# MCU.net
KiCad netlist of a schematic drawn in Altium Designer
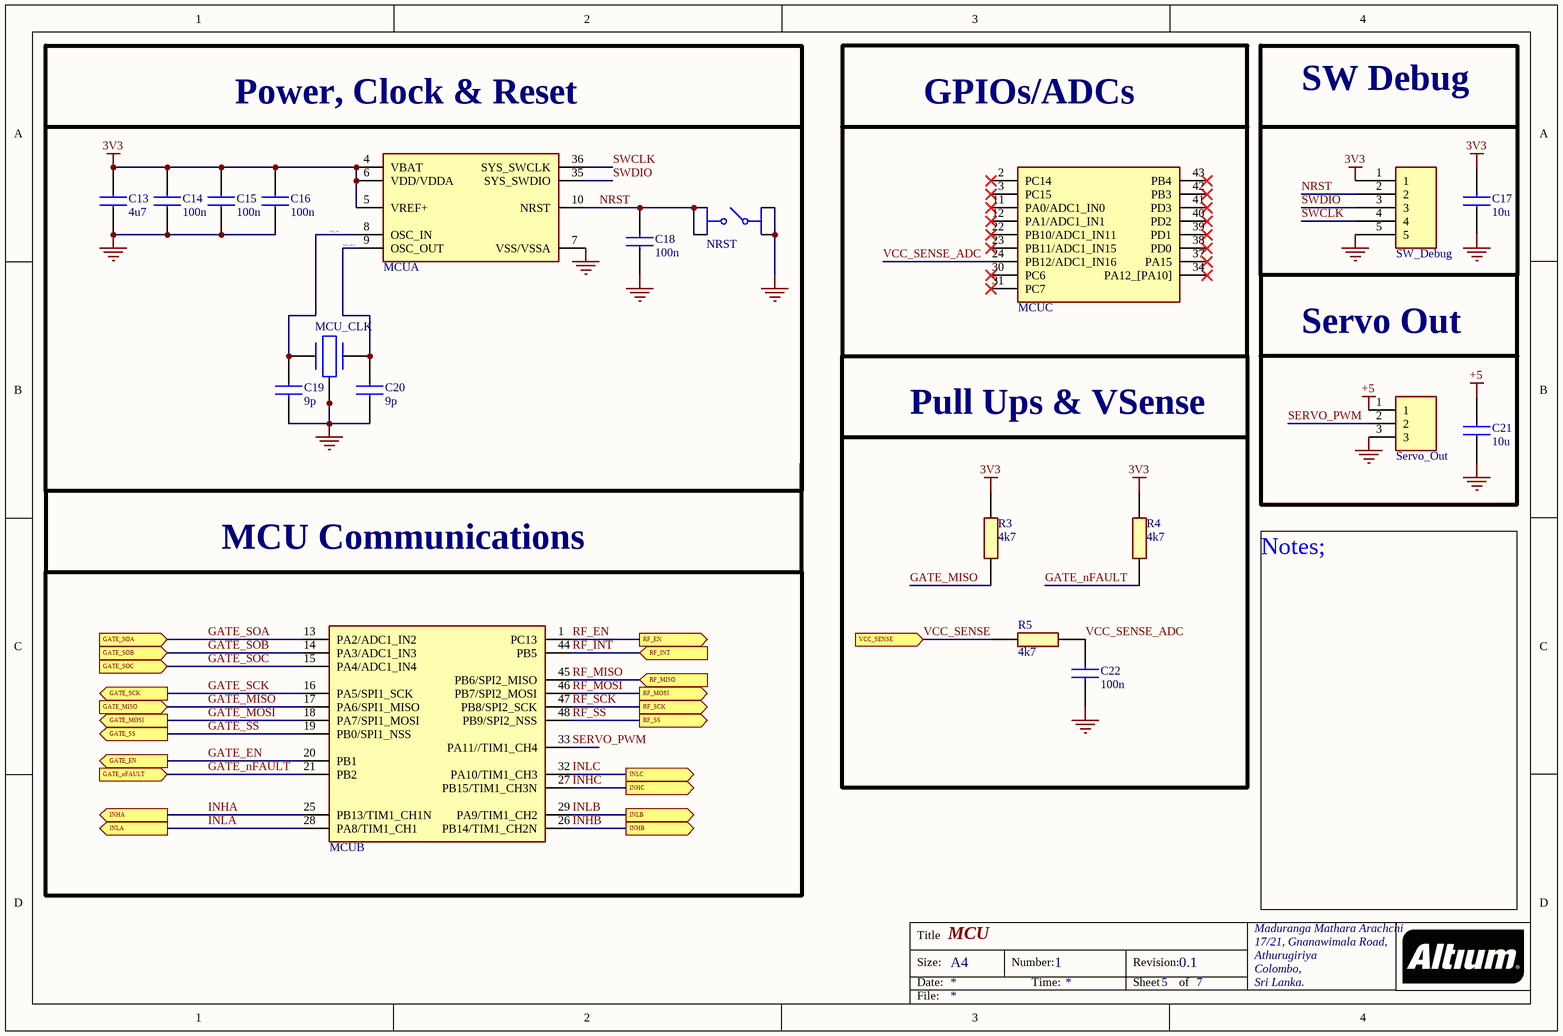
[diagram p0: MCU.SchDoc]

(export (version "E")
  (design (tool "Eeschema 10.0.6"))
  (components
    (comp (ref "C13")
      (value "4u7")
      (footprint "RC_Car:CAPC1608X90N")
      (description "Capacitor")
      (fields
        (field (name "MANUFACTURER_PART_NUMBER") "GRM188R61E475ME11J")
        (field (name "MOUSER PART NUMBER") "81-GRM188R61E475ME1J")
      )
      (libsource (lib "RC_Car") (part "GRM188R61E475ME11J"))
    )
    (comp (ref "C14")
      (value "100n")
      (footprint "RC_Car:GRM18x")
      (description "Capacitor")
      (fields
        (field (name "MANUFACTURER_PART_NUMBER") "GRM188R72A104KA35D")
        (field (name "MOUSER PART NUMBER") "81-GRM188R72A104KA35")
      )
      (libsource (lib "RC_Car") (part "GRM188R72A104KA35D"))
    )
    (comp (ref "C15")
      (value "100n")
      (footprint "RC_Car:GRM18x")
      (description "Capacitor")
      (fields
        (field (name "MANUFACTURER_PART_NUMBER") "GRM188R72A104KA35D")
        (field (name "MOUSER PART NUMBER") "81-GRM188R72A104KA35")
      )
      (libsource (lib "RC_Car") (part "GRM188R72A104KA35D"))
    )
    (comp (ref "C16")
      (value "100n")
      (footprint "RC_Car:GRM18x")
      (description "Capacitor")
      (fields
        (field (name "MANUFACTURER_PART_NUMBER") "GRM188R72A104KA35D")
        (field (name "MOUSER PART NUMBER") "81-GRM188R72A104KA35")
      )
      (libsource (lib "RC_Car") (part "GRM188R72A104KA35D"))
    )
    (comp (ref "C17")
      (value "10u")
      (footprint "RC_Car:CAPC1608X90N")
      (description "Capacitor")
      (fields (field (name "MANUFACTURER_PART_NUMBER") "C0603C106M9PAC-TU"))
      (libsource (lib "RC_Car") (part "C0603C106M9PAC-TU"))
    )
    (comp (ref "C18")
      (value "100n")
      (footprint "RC_Car:GRM18x")
      (description "Capacitor")
      (fields
        (field (name "MANUFACTURER_PART_NUMBER") "GRM188R72A104KA35D")
        (field (name "MOUSER PART NUMBER") "81-GRM188R72A104KA35")
      )
      (libsource (lib "RC_Car") (part "GRM188R72A104KA35D"))
    )
    (comp (ref "C19")
      (value "9p")
      (footprint "RC_Car:CAPC1005X70N")
      (description "Capacitor")
      (fields (field (name "MANUFACTURER_PART_NUMBER") "GRM1555C1E9R0WA01J"))
      (libsource (lib "RC_Car") (part "GRM1555C1E9R0WA01J"))
    )
    (comp (ref "C20")
      (value "9p")
      (footprint "RC_Car:CAPC1005X70N")
      (description "Capacitor")
      (fields (field (name "MANUFACTURER_PART_NUMBER") "GRM1555C1E9R0WA01J"))
      (libsource (lib "RC_Car") (part "GRM1555C1E9R0WA01J"))
    )
    (comp (ref "C21")
      (value "10u")
      (footprint "RC_Car:CAPC1608X90N")
      (description "Capacitor")
      (fields (field (name "MANUFACTURER_PART_NUMBER") "C0603C106M9PAC-TU"))
      (libsource (lib "RC_Car") (part "C0603C106M9PAC-TU"))
    )
    (comp (ref "C22")
      (value "100n")
      (footprint "RC_Car:GRM18x")
      (description "Capacitor")
      (fields
        (field (name "MANUFACTURER_PART_NUMBER") "GRM188R72A104KA35D")
        (field (name "MOUSER PART NUMBER") "81-GRM188R72A104KA35")
      )
      (libsource (lib "RC_Car") (part "GRM188R72A104KA35D"))
    )
    (comp (ref "MCU")
      (value "STM32G070CBT6TR")
      (footprint "RC_Car:QFP50P900X900X160-48N")
      (description "Integrated Circuit")
      (fields (field (name "MOUSER PART NUMBER") "511-STM32G070CBT6TR"))
      (libsource (lib "RC_Car") (part "STM32G070CBT6TR"))
    )
    (comp (ref "MCU_CLK")
      (value "TSX-3225_16.0000MF18X-AC0")
      (footprint "RC_Car:TSX3225160000MF18XAC0")
      (description "16MHz Crystal")
      (fields
        (field (name "MANUFACTURER_PART_NUMBER") "TSX-3225 16.0000MF18X-AC0")
        (field (name "MOUSER PART NUMBER") "732-322516F18XAC0")
      )
      (libsource (lib "RC_Car") (part "TSX-3225_16.0000MF18X-AC0"))
    )
    (comp (ref "NRST")
      (value "PTS647SM50SMTR2N_LFS")
      (footprint "RC_Car:PTS647SK50SMTR2LFS")
      (description "Switch (4-Pin Push)")
      (fields (field (name "MANUFACTURER_PART_NUMBER") "PTS647SM50SMTR2N LFS"))
      (libsource (lib "RC_Car") (part "PTS647SM50SMTR2N_LFS"))
    )
    (comp (ref "R3")
      (value "4k7")
      (footprint "RC_Car:RESC1608X50N")
      (description "Resistor")
      (fields
        (field (name "MANUFACTURER_PART_NUMBER") "CRCW06034K70FKEC")
        (field (name "MOUSER PART NUMBER") "71-CRCW06034K70FKEC")
      )
      (libsource (lib "RC_Car") (part "CRCW06034K70FKEC"))
    )
    (comp (ref "R4")
      (value "4k7")
      (footprint "RC_Car:RESC1608X50N")
      (description "Resistor")
      (fields
        (field (name "MANUFACTURER_PART_NUMBER") "CRCW06034K70FKEC")
        (field (name "MOUSER PART NUMBER") "71-CRCW06034K70FKEC")
      )
      (libsource (lib "RC_Car") (part "CRCW06034K70FKEC"))
    )
    (comp (ref "R5")
      (value "4k7")
      (footprint "RC_Car:RESC1608X50N")
      (description "Resistor")
      (fields
        (field (name "MANUFACTURER_PART_NUMBER") "CRCW06034K70FKEC")
        (field (name "MOUSER PART NUMBER") "71-CRCW06034K70FKEC")
      )
      (libsource (lib "") (part "CRCW06034K70FKEC_1"))
    )
    (comp (ref "Servo_Out")
      (value "929850-01-03-RA")
      (footprint "RC_Car:RHDR3W76P0X254_1X3_762X254X826P")
      (description "Header")
      (fields (field (name "MOUSER PART NUMBER") "517-929850-01-03-RA"))
      (libsource (lib "RC_Car") (part "929850-01-03-RA"))
    )
    (comp (ref "SW_Debug")
      (value "SW Debug")
      (footprint "SW_Debug")
      (libsource (lib "RC_Car") (part "Debug Pads"))
    )
  )
  (nets
    (net (code "1") (name "+5") (class "Default")
      (node (ref "C21") (pin "2") (pinfunction "2_2") (pintype "passive"))
      (node (ref "Servo_Out") (pin "1") (pinfunction "1_1") (pintype "passive"))
    )
    (net (code "2") (name "/GATE_EN") (class "Default")
      (node (ref "MCU") (pin "20") (pinfunction "PB1_20") (pintype "passive"))
    )
    (net (code "3") (name "/GATE_MISO") (class "Default")
      (node (ref "MCU") (pin "17") (pinfunction "PA6/SPI1_MISO_17") (pintype "passive"))
      (node (ref "R3") (pin "1") (pinfunction "1_1") (pintype "passive"))
    )
    (net (code "4") (name "/GATE_MOSI") (class "Default")
      (node (ref "MCU") (pin "18") (pinfunction "PA7/SPI1_MOSI_18") (pintype "passive"))
    )
    (net (code "5") (name "/GATE_SCK") (class "Default")
      (node (ref "MCU") (pin "16") (pinfunction "PA5/SPI1_SCK_16") (pintype "passive"))
    )
    (net (code "6") (name "/GATE_SOA") (class "Default")
      (node (ref "MCU") (pin "13") (pinfunction "PA2/ADC1_IN2_13") (pintype "passive"))
    )
    (net (code "7") (name "/GATE_SOB") (class "Default")
      (node (ref "MCU") (pin "14") (pinfunction "PA3/ADC1_IN3_14") (pintype "passive"))
    )
    (net (code "8") (name "/GATE_SOC") (class "Default")
      (node (ref "MCU") (pin "15") (pinfunction "PA4/ADC1_IN4_15") (pintype "passive"))
    )
    (net (code "9") (name "/GATE_SS") (class "Default")
      (node (ref "MCU") (pin "19") (pinfunction "PB0/SPI1_NSS_19") (pintype "passive"))
    )
    (net (code "10") (name "/GATE_nFAULT") (class "Default")
      (node (ref "MCU") (pin "21") (pinfunction "PB2_21") (pintype "passive"))
      (node (ref "R4") (pin "1") (pinfunction "1_1") (pintype "passive"))
    )
    (net (code "11") (name "/INHA") (class "Default")
      (node (ref "MCU") (pin "25") (pinfunction "PB13/TIM1_CH1N_25") (pintype "passive"))
    )
    (net (code "12") (name "/INHB") (class "Default")
      (node (ref "MCU") (pin "26") (pinfunction "PB14/TIM1_CH2N_26") (pintype "passive"))
    )
    (net (code "13") (name "/INHC") (class "Default")
      (node (ref "MCU") (pin "27") (pinfunction "PB15/TIM1_CH3N_27") (pintype "passive"))
    )
    (net (code "14") (name "/INLA") (class "Default")
      (node (ref "MCU") (pin "28") (pinfunction "PA8/TIM1_CH1_28") (pintype "passive"))
    )
    (net (code "15") (name "/INLB") (class "Default")
      (node (ref "MCU") (pin "29") (pinfunction "PA9/TIM1_CH2_29") (pintype "passive"))
    )
    (net (code "16") (name "/INLC") (class "Default")
      (node (ref "MCU") (pin "32") (pinfunction "PA10/TIM1_CH3_32") (pintype "passive"))
    )
    (net (code "17") (name "/NRST") (class "Default")
      (node (ref "C18") (pin "2") (pinfunction "2_2") (pintype "passive"))
      (node (ref "MCU") (pin "10") (pinfunction "NRST_10") (pintype "passive"))
      (node (ref "NRST") (pin "1") (pinfunction "NO_1_1") (pintype "passive"))
      (node (ref "NRST") (pin "2") (pinfunction "NO_2_2") (pintype "passive"))
      (node (ref "SW_Debug") (pin "2") (pinfunction "2_2") (pintype "passive"))
    )
    (net (code "18") (name "/OSC_IN") (class "Default")
      (node (ref "C19") (pin "2") (pinfunction "2_2") (pintype "passive"))
      (node (ref "MCU") (pin "8") (pinfunction "OSC_IN_8") (pintype "passive"))
      (node (ref "MCU_CLK") (pin "1") (pinfunction "CRYSTAL_1_1") (pintype "passive"))
    )
    (net (code "19") (name "/OSC_OUT") (class "Default")
      (node (ref "C20") (pin "2") (pinfunction "2_2") (pintype "passive"))
      (node (ref "MCU") (pin "9") (pinfunction "OSC_OUT_9") (pintype "passive"))
      (node (ref "MCU_CLK") (pin "3") (pinfunction "CRYSTAL_2_3") (pintype "passive"))
    )
    (net (code "20") (name "/RF_EN") (class "Default")
      (node (ref "MCU") (pin "1") (pinfunction "PC13_1") (pintype "passive"))
    )
    (net (code "21") (name "/RF_INT") (class "Default")
      (node (ref "MCU") (pin "44") (pinfunction "PB5_44") (pintype "passive"))
    )
    (net (code "22") (name "/RF_MISO") (class "Default")
      (node (ref "MCU") (pin "45") (pinfunction "PB6/SPI2_MISO_45") (pintype "passive"))
    )
    (net (code "23") (name "/RF_MOSI") (class "Default")
      (node (ref "MCU") (pin "46") (pinfunction "PB7/SPI2_MOSI_46") (pintype "passive"))
    )
    (net (code "24") (name "/RF_SCK") (class "Default")
      (node (ref "MCU") (pin "47") (pinfunction "PB8/SPI2_SCK_47") (pintype "passive"))
    )
    (net (code "25") (name "/RF_SS") (class "Default")
      (node (ref "MCU") (pin "48") (pinfunction "PB9/SPI2_NSS_48") (pintype "passive"))
    )
    (net (code "26") (name "/SERVO_PWM") (class "Default")
      (node (ref "MCU") (pin "33") (pinfunction "PA11//TIM1_CH4_33") (pintype "passive"))
      (node (ref "Servo_Out") (pin "2") (pinfunction "2_2") (pintype "passive"))
    )
    (net (code "27") (name "/SWCLK") (class "Default")
      (node (ref "MCU") (pin "36") (pinfunction "SYS_SWCLK_36") (pintype "passive"))
      (node (ref "SW_Debug") (pin "4") (pinfunction "4_4") (pintype "passive"))
    )
    (net (code "28") (name "/SWDIO") (class "Default")
      (node (ref "MCU") (pin "35") (pinfunction "SYS_SWDIO_35") (pintype "passive"))
      (node (ref "SW_Debug") (pin "3") (pinfunction "3_3") (pintype "passive"))
    )
    (net (code "29") (name "/VCC_SENSE") (class "Default")
      (node (ref "R5") (pin "2") (pinfunction "2_2") (pintype "passive"))
    )
    (net (code "30") (name "/VCC_SENSE_ADC") (class "Default")
      (node (ref "C22") (pin "2") (pinfunction "2_2") (pintype "passive"))
      (node (ref "MCU") (pin "24") (pinfunction "PB12/ADC1_IN16_24") (pintype "passive"))
      (node (ref "R5") (pin "1") (pinfunction "1_1") (pintype "passive"))
    )
    (net (code "31") (name "3V3") (class "Default")
      (node (ref "C13") (pin "1") (pinfunction "1_1") (pintype "passive"))
      (node (ref "C14") (pin "2") (pinfunction "2_2") (pintype "passive"))
      (node (ref "C15") (pin "2") (pinfunction "2_2") (pintype "passive"))
      (node (ref "C16") (pin "2") (pinfunction "2_2") (pintype "passive"))
      (node (ref "C17") (pin "2") (pinfunction "2_2") (pintype "passive"))
      (node (ref "MCU") (pin "4") (pinfunction "VBAT_4") (pintype "passive"))
      (node (ref "MCU") (pin "5") (pinfunction "VREF+_5") (pintype "passive"))
      (node (ref "MCU") (pin "6") (pinfunction "VDD/VDDA_6") (pintype "passive"))
      (node (ref "R3") (pin "2") (pinfunction "2_2") (pintype "passive"))
      (node (ref "R4") (pin "2") (pinfunction "2_2") (pintype "passive"))
      (node (ref "SW_Debug") (pin "1") (pinfunction "1_1") (pintype "passive"))
    )
    (net (code "32") (name "GND") (class "Default")
      (node (ref "C13") (pin "2") (pinfunction "2_2") (pintype "passive"))
      (node (ref "C14") (pin "1") (pinfunction "1_1") (pintype "passive"))
      (node (ref "C15") (pin "1") (pinfunction "1_1") (pintype "passive"))
      (node (ref "C16") (pin "1") (pinfunction "1_1") (pintype "passive"))
      (node (ref "C17") (pin "1") (pinfunction "1_1") (pintype "passive"))
      (node (ref "C18") (pin "1") (pinfunction "1_1") (pintype "passive"))
      (node (ref "C19") (pin "1") (pinfunction "1_1") (pintype "passive"))
      (node (ref "C20") (pin "1") (pinfunction "1_1") (pintype "passive"))
      (node (ref "C21") (pin "1") (pinfunction "1_1") (pintype "passive"))
      (node (ref "C22") (pin "1") (pinfunction "1_1") (pintype "passive"))
      (node (ref "MCU") (pin "7") (pinfunction "VSS/VSSA_7") (pintype "passive"))
      (node (ref "MCU_CLK") (pin "2") (pinfunction "GND_1_2") (pintype "passive"))
      (node (ref "MCU_CLK") (pin "4") (pinfunction "GND_2_4") (pintype "passive"))
      (node (ref "NRST") (pin "3") (pinfunction "COM_1_3") (pintype "passive"))
      (node (ref "NRST") (pin "4") (pinfunction "COM_2_4") (pintype "passive"))
      (node (ref "SW_Debug") (pin "5") (pinfunction "5_5") (pintype "passive"))
      (node (ref "Servo_Out") (pin "3") (pinfunction "3_3") (pintype "passive"))
    )
    (net (code "33") (name "unconnected-(MCUC-PA0{slash}ADC1_IN0-Pad11)") (class "Default")
      (node (ref "MCU") (pin "11") (pinfunction "PA0/ADC1_IN0_11") (pintype "passive+no_connect"))
    )
    (net (code "34") (name "unconnected-(MCUC-PA1{slash}ADC1_IN1-Pad12)") (class "Default")
      (node (ref "MCU") (pin "12") (pinfunction "PA1/ADC1_IN1_12") (pintype "passive+no_connect"))
    )
    (net (code "35") (name "unconnected-(MCUC-PA12_[PA10]-Pad34)") (class "Default")
      (node (ref "MCU") (pin "34") (pinfunction "PA12_[PA10]_34") (pintype "passive+no_connect"))
    )
    (net (code "36") (name "unconnected-(MCUC-PA15-Pad37)") (class "Default")
      (node (ref "MCU") (pin "37") (pinfunction "PA15_37") (pintype "passive+no_connect"))
    )
    (net (code "37") (name "unconnected-(MCUC-PB3-Pad42)") (class "Default")
      (node (ref "MCU") (pin "42") (pinfunction "PB3_42") (pintype "passive+no_connect"))
    )
    (net (code "38") (name "unconnected-(MCUC-PB4-Pad43)") (class "Default")
      (node (ref "MCU") (pin "43") (pinfunction "PB4_43") (pintype "passive+no_connect"))
    )
    (net (code "39") (name "unconnected-(MCUC-PB10{slash}ADC1_IN11-Pad22)") (class "Default")
      (node (ref "MCU") (pin "22") (pinfunction "PB10/ADC1_IN11_22") (pintype "passive+no_connect"))
    )
    (net (code "40") (name "unconnected-(MCUC-PB11{slash}ADC1_IN15-Pad23)") (class "Default")
      (node (ref "MCU") (pin "23") (pinfunction "PB11/ADC1_IN15_23") (pintype "passive+no_connect"))
    )
    (net (code "41") (name "unconnected-(MCUC-PC6-Pad30)") (class "Default")
      (node (ref "MCU") (pin "30") (pinfunction "PC6_30") (pintype "passive+no_connect"))
    )
    (net (code "42") (name "unconnected-(MCUC-PC7-Pad31)") (class "Default")
      (node (ref "MCU") (pin "31") (pinfunction "PC7_31") (pintype "passive+no_connect"))
    )
    (net (code "43") (name "unconnected-(MCUC-PC14-Pad2)") (class "Default")
      (node (ref "MCU") (pin "2") (pinfunction "PC14_2") (pintype "passive+no_connect"))
    )
    (net (code "44") (name "unconnected-(MCUC-PC15-Pad3)") (class "Default")
      (node (ref "MCU") (pin "3") (pinfunction "PC15_3") (pintype "passive+no_connect"))
    )
    (net (code "45") (name "unconnected-(MCUC-PD0-Pad38)") (class "Default")
      (node (ref "MCU") (pin "38") (pinfunction "PD0_38") (pintype "passive+no_connect"))
    )
    (net (code "46") (name "unconnected-(MCUC-PD1-Pad39)") (class "Default")
      (node (ref "MCU") (pin "39") (pinfunction "PD1_39") (pintype "passive+no_connect"))
    )
    (net (code "47") (name "unconnected-(MCUC-PD2-Pad40)") (class "Default")
      (node (ref "MCU") (pin "40") (pinfunction "PD2_40") (pintype "passive+no_connect"))
    )
    (net (code "48") (name "unconnected-(MCUC-PD3-Pad41)") (class "Default")
      (node (ref "MCU") (pin "41") (pinfunction "PD3_41") (pintype "passive+no_connect"))
    )
  )
)
